# irthrowie.net
KiCad netlist of a schematic drawn in EAGLE
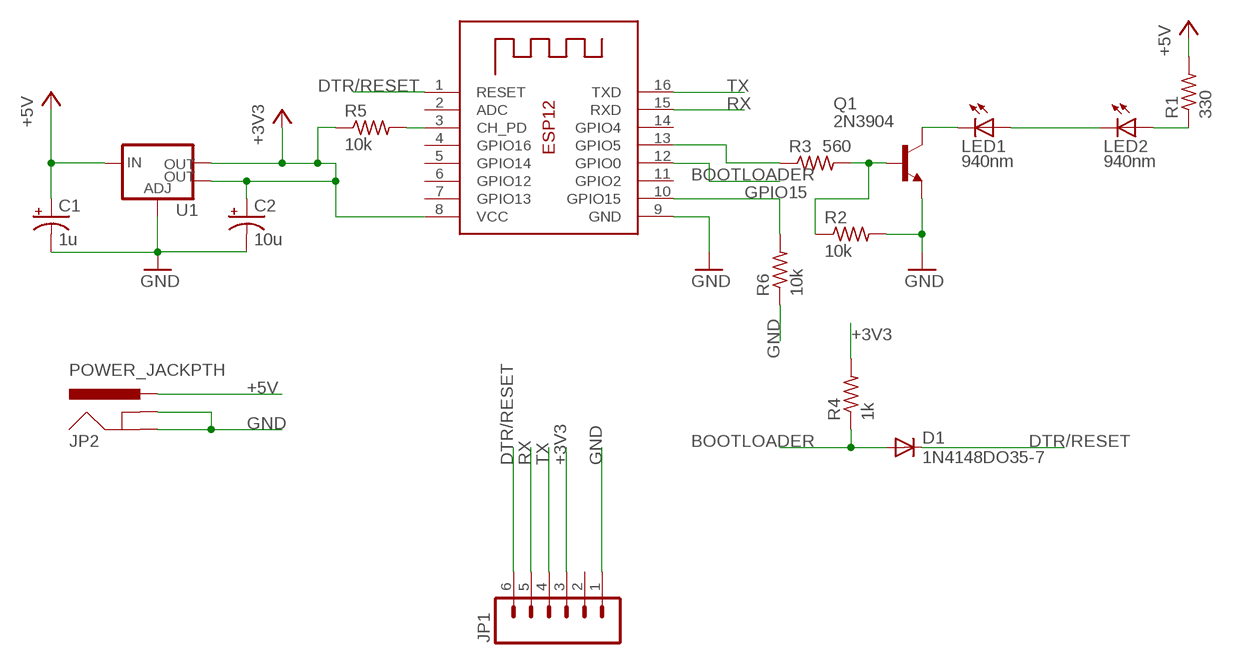
[diagram p0: schematic, sheet 1]

(export (version "E")
  (design (tool "Eeschema 10.0.6"))
  (components
    (comp (ref "C1")
      (value "1u")
      (footprint "eagle-import:PANASONIC_B")
      (libsource (lib "eagle-import") (part "CPOL-USB"))
    )
    (comp (ref "C2")
      (value "10u")
      (footprint "eagle-import:PANASONIC_B")
      (libsource (lib "eagle-import") (part "CPOL-USB"))
    )
    (comp (ref "D1")
      (value "1N4148DO35-7")
      (footprint "eagle-import:DO35-7")
      (libsource (lib "eagle-import") (part "1N4148DO35-7"))
    )
    (comp (ref "JP1")
      (value "M06LOCK")
      (footprint "eagle-import:1X06_LOCK")
      (libsource (lib "eagle-import") (part "M06LOCK"))
    )
    (comp (ref "JP2")
      (value "POWER_JACKPTH")
      (footprint "eagle-import:POWER_JACK_PTH")
      (libsource (lib "eagle-import") (part "POWER_JACKPTH"))
    )
    (comp (ref "LED1")
      (value "940nm")
      (footprint "eagle-import:LED5MM")
      (libsource (lib "eagle-import") (part "LED5MM"))
    )
    (comp (ref "LED2")
      (value "940nm")
      (footprint "eagle-import:LED5MM")
      (libsource (lib "eagle-import") (part "LED5MM"))
    )
    (comp (ref "Q1")
      (value "2N3904")
      (footprint "eagle-import:TO92")
      (libsource (lib "eagle-import") (part "2N3904"))
    )
    (comp (ref "R1")
      (value "330")
      (footprint "eagle-import:0204_7")
      (libsource (lib "eagle-import") (part "R-US_0204/7"))
    )
    (comp (ref "R2")
      (value "10k")
      (footprint "eagle-import:0204_7")
      (libsource (lib "eagle-import") (part "R-US_0204/7"))
    )
    (comp (ref "R3")
      (value "560")
      (footprint "eagle-import:0204_7")
      (libsource (lib "eagle-import") (part "R-US_0204/7"))
    )
    (comp (ref "R4")
      (value "1k")
      (footprint "eagle-import:0204_7")
      (libsource (lib "eagle-import") (part "R-US_0204/7"))
    )
    (comp (ref "R5")
      (value "10k")
      (footprint "eagle-import:0204_7")
      (libsource (lib "eagle-import") (part "R-US_0204/7"))
    )
    (comp (ref "R6")
      (value "10k")
      (footprint "eagle-import:0204_7")
      (libsource (lib "eagle-import") (part "R-US_0204/7"))
    )
    (comp (ref "U1")
      (value "V_REG_LM1117SOT223")
      (footprint "eagle-import:SOT223")
      (libsource (lib "eagle-import") (part "V_REG_LM1117SOT223"))
    )
    (comp (ref "X1")
      (value "ESP-12")
      (footprint "eagle-import:ESP-12")
      (libsource (lib "eagle-import") (part "ESP-12"))
    )
  )
  (nets
    (net (code "1") (name "+3V3") (class "Default")
      (node (ref "C2") (pin "+") (pinfunction "+_+") (pintype "passive"))
      (node (ref "JP1") (pin "3") (pinfunction "3_3") (pintype "passive"))
      (node (ref "R4") (pin "2") (pinfunction "2_2") (pintype "passive"))
      (node (ref "R5") (pin "1") (pinfunction "1_1") (pintype "passive"))
      (node (ref "U1") (pin "2") (pinfunction "OUT_2") (pintype "output"))
      (node (ref "U1") (pin "4") (pinfunction "OUT_4") (pintype "output"))
      (node (ref "X1") (pin "8") (pinfunction "VCC_8") (pintype "power_in"))
    )
    (net (code "2") (name "+5V") (class "Default")
      (node (ref "C1") (pin "+") (pinfunction "+_+") (pintype "passive"))
      (node (ref "JP2") (pin "PWR") (pinfunction "PWR_PWR") (pintype "bidirectional"))
      (node (ref "R1") (pin "2") (pinfunction "2_2") (pintype "passive"))
      (node (ref "U1") (pin "3") (pinfunction "IN_3") (pintype "input"))
    )
    (net (code "3") (name "/BOOTLOADER") (class "Default")
      (node (ref "D1") (pin "A") (pinfunction "A_A") (pintype "passive"))
      (node (ref "R4") (pin "1") (pinfunction "1_1") (pintype "passive"))
      (node (ref "X1") (pin "12") (pinfunction "GPIO0_12") (pintype "bidirectional"))
    )
    (net (code "4") (name "/DTR{slash}RESET") (class "Default")
      (node (ref "D1") (pin "C") (pinfunction "C_C") (pintype "passive"))
      (node (ref "JP1") (pin "6") (pinfunction "6_6") (pintype "passive"))
      (node (ref "X1") (pin "1") (pinfunction "RESET_1") (pintype "input"))
    )
    (net (code "5") (name "/GPIO15") (class "Default")
      (node (ref "R6") (pin "2") (pinfunction "2_2") (pintype "passive"))
      (node (ref "X1") (pin "10") (pinfunction "GPIO15_10") (pintype "bidirectional"))
    )
    (net (code "6") (name "/RX") (class "Default")
      (node (ref "JP1") (pin "5") (pinfunction "5_5") (pintype "passive"))
      (node (ref "X1") (pin "15") (pinfunction "RXD_15") (pintype "input"))
    )
    (net (code "7") (name "/TX") (class "Default")
      (node (ref "JP1") (pin "4") (pinfunction "4_4") (pintype "passive"))
      (node (ref "X1") (pin "16") (pinfunction "TXD_16") (pintype "output"))
    )
    (net (code "8") (name "GND") (class "Default")
      (node (ref "C1") (pin "-") (pinfunction "-_-") (pintype "passive"))
      (node (ref "C2") (pin "-") (pinfunction "-_-") (pintype "passive"))
      (node (ref "JP1") (pin "1") (pinfunction "1_1") (pintype "passive"))
      (node (ref "JP2") (pin "GND") (pinfunction "GND_GND") (pintype "bidirectional"))
      (node (ref "JP2") (pin "GNDBREAK") (pinfunction "GNDBREAK_GNDBREAK") (pintype "bidirectional"))
      (node (ref "Q1") (pin "3") (pinfunction "E_3") (pintype "passive"))
      (node (ref "R2") (pin "2") (pinfunction "2_2") (pintype "passive"))
      (node (ref "R6") (pin "1") (pinfunction "1_1") (pintype "passive"))
      (node (ref "U1") (pin "1") (pinfunction "ADJ_1") (pintype "input"))
      (node (ref "X1") (pin "9") (pinfunction "GND_9") (pintype "power_in"))
    )
    (net (code "9") (name "Net-(LED1-C)") (class "Default")
      (node (ref "LED1") (pin "K") (pinfunction "C_K") (pintype "passive"))
      (node (ref "Q1") (pin "1") (pinfunction "C_1") (pintype "passive"))
    )
    (net (code "10") (name "Net-(LED2-C)") (class "Default")
      (node (ref "LED1") (pin "A") (pinfunction "A_A") (pintype "passive"))
      (node (ref "LED2") (pin "K") (pinfunction "C_K") (pintype "passive"))
    )
    (net (code "11") (name "Net-(LED2-PadA)") (class "Default")
      (node (ref "LED2") (pin "A") (pinfunction "A_A") (pintype "passive"))
      (node (ref "R1") (pin "1") (pinfunction "1_1") (pintype "passive"))
    )
    (net (code "12") (name "Net-(Q1-B)") (class "Default")
      (node (ref "Q1") (pin "2") (pinfunction "B_2") (pintype "passive"))
      (node (ref "R2") (pin "1") (pinfunction "1_1") (pintype "passive"))
      (node (ref "R3") (pin "2") (pinfunction "2_2") (pintype "passive"))
    )
    (net (code "13") (name "Net-(X1-CH_PD)") (class "Default")
      (node (ref "R5") (pin "2") (pinfunction "2_2") (pintype "passive"))
      (node (ref "X1") (pin "3") (pinfunction "CH_PD_3") (pintype "input"))
    )
    (net (code "14") (name "Net-(X1-GPIO5)") (class "Default")
      (node (ref "R3") (pin "1") (pinfunction "1_1") (pintype "passive"))
      (node (ref "X1") (pin "13") (pinfunction "GPIO5_13") (pintype "bidirectional"))
    )
    (net (code "15") (name "unconnected-(JP1-Pad2)") (class "Default")
      (node (ref "JP1") (pin "2") (pinfunction "2_2") (pintype "passive"))
    )
    (net (code "16") (name "unconnected-(X1-ADC-Pad2)") (class "Default")
      (node (ref "X1") (pin "2") (pinfunction "ADC_2") (pintype "passive"))
    )
    (net (code "17") (name "unconnected-(X1-GPIO2-Pad11)") (class "Default")
      (node (ref "X1") (pin "11") (pinfunction "GPIO2_11") (pintype "bidirectional"))
    )
    (net (code "18") (name "unconnected-(X1-GPIO4-Pad14)") (class "Default")
      (node (ref "X1") (pin "14") (pinfunction "GPIO4_14") (pintype "bidirectional"))
    )
    (net (code "19") (name "unconnected-(X1-GPIO12-Pad6)") (class "Default")
      (node (ref "X1") (pin "6") (pinfunction "GPIO12_6") (pintype "bidirectional"))
    )
    (net (code "20") (name "unconnected-(X1-GPIO13-Pad7)") (class "Default")
      (node (ref "X1") (pin "7") (pinfunction "GPIO13_7") (pintype "bidirectional"))
    )
    (net (code "21") (name "unconnected-(X1-GPIO14-Pad5)") (class "Default")
      (node (ref "X1") (pin "5") (pinfunction "GPIO14_5") (pintype "bidirectional"))
    )
    (net (code "22") (name "unconnected-(X1-GPIO16-Pad4)") (class "Default")
      (node (ref "X1") (pin "4") (pinfunction "GPIO16_4") (pintype "bidirectional"))
    )
  )
)
